# Microcontroller.net
KiCad netlist of a schematic drawn in Altium Designer
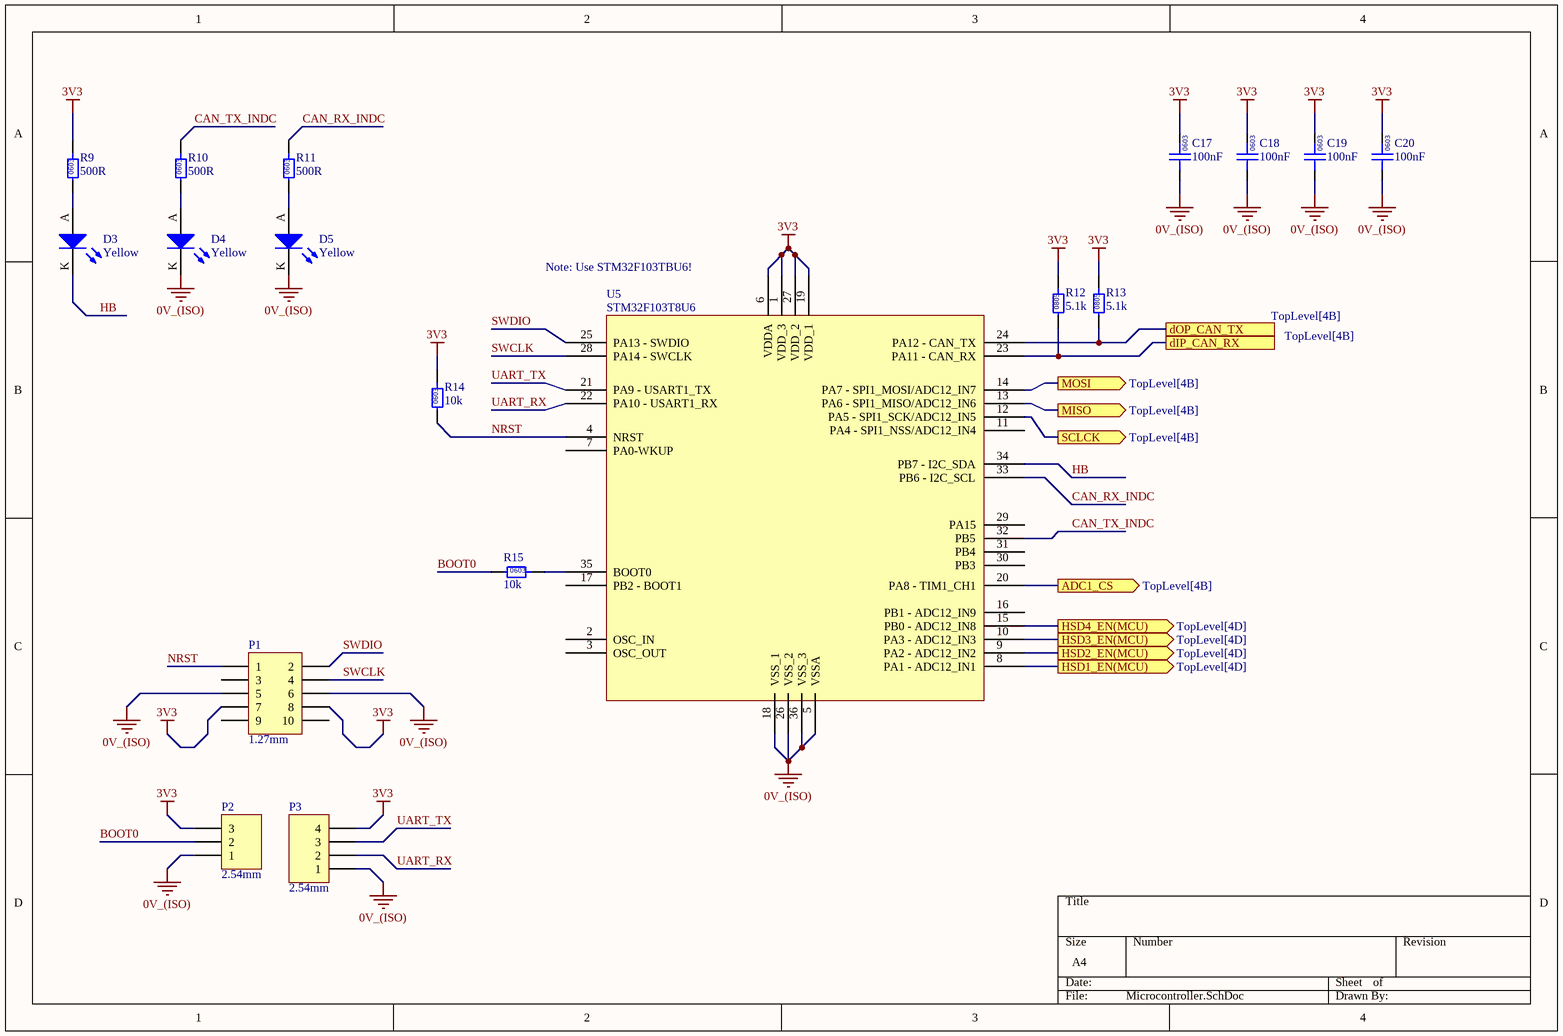
[diagram p0: Microcontroller.SchDoc]

(export (version "E")
  (design (tool "Eeschema 10.0.6"))
  (components
    (comp (ref "C17")
      (value "100nF")
      (footprint "0603")
      (fields
        (field (name "PART NUMBER") "GCM188L81H104KA57D")
        (field (name "MANUFACTURER") "muRata")
        (field (name "TOLERANCE") "±10%")
      )
      (libsource (lib "ts_standard_library") (part "Capacitor 0603"))
    )
    (comp (ref "C18")
      (value "100nF")
      (footprint "0603")
      (fields
        (field (name "PART NUMBER") "GCM188L81H104KA57D")
        (field (name "MANUFACTURER") "muRata")
        (field (name "TOLERANCE") "±10%")
      )
      (libsource (lib "ts_standard_library") (part "Capacitor 0603"))
    )
    (comp (ref "C19")
      (value "100nF")
      (footprint "0603")
      (fields
        (field (name "PART NUMBER") "GCM188L81H104KA57D")
        (field (name "MANUFACTURER") "muRata")
        (field (name "TOLERANCE") "±10%")
      )
      (libsource (lib "ts_standard_library") (part "Capacitor 0603"))
    )
    (comp (ref "C20")
      (value "100nF")
      (footprint "0603")
      (fields
        (field (name "PART NUMBER") "GCM188L81H104KA57D")
        (field (name "MANUFACTURER") "muRata")
        (field (name "TOLERANCE") "±10%")
      )
      (libsource (lib "ts_standard_library") (part "Capacitor 0603"))
    )
    (comp (ref "D3")
      (value "Yellow")
      (footprint "0805 LED")
      (description "Yellow LED Indication - Discrete 1.75V 0805 (2012 Metric)")
      (fields (field (name "PART NUMBER") "SML-211YTT86") (field (name "MANUFACTURER") "ROHM Semiconductor"))
      (libsource (lib "ts_standard_library") (part "LED"))
    )
    (comp (ref "D4")
      (value "Yellow")
      (footprint "0805 LED")
      (description "Yellow LED Indication - Discrete 1.75V 0805 (2012 Metric)")
      (fields (field (name "PART NUMBER") "SML-211YTT86") (field (name "MANUFACTURER") "ROHM Semiconductor"))
      (libsource (lib "ts_standard_library") (part "LED"))
    )
    (comp (ref "D5")
      (value "Yellow")
      (footprint "0805 LED")
      (description "Yellow LED Indication - Discrete 1.75V 0805 (2012 Metric)")
      (fields (field (name "PART NUMBER") "SML-211YTT86") (field (name "MANUFACTURER") "ROHM Semiconductor"))
      (libsource (lib "ts_standard_library") (part "LED"))
    )
    (comp (ref "P1")
      (value "1.27mm")
      (footprint "3221-10-0300-00")
      (fields
        (field (name "PART NUMBER") "SMD 1.27mm Header 2x5 (3221-10-0300-00)")
        (field (name "CONTACT") "NA")
      )
      (libsource (lib "ts_standard_connectors") (part "Header 2x5"))
    )
    (comp (ref "P2")
      (value "2.54mm")
      (footprint "TH 2.54mm Header 1x3")
      (fields (field (name "PART NUMBER") "TH 2.54mm Header 1x3") (field (name "CONTACT") "NA"))
      (libsource (lib "ts_standard_connectors") (part "Header 1x3"))
    )
    (comp (ref "P3")
      (value "2.54mm")
      (footprint "TH 2.54mm Header 1x4")
      (fields (field (name "PART NUMBER") "TH 2.54mm Header 1x4") (field (name "CONTACT") "NA"))
      (libsource (lib "ts_standard_connectors") (part "Header 1x4"))
    )
    (comp (ref "R9")
      (value "500R")
      (footprint "0603")
      (fields
        (field (name "PART NUMBER") "RT0603BRD07500RL")
        (field (name "MANUFACTURER") "YAGEO")
        (field (name "TOLERANCE") "0.01")
      )
      (libsource (lib "ts_standard_library") (part "Resistor 0603"))
    )
    (comp (ref "R10")
      (value "500R")
      (footprint "0603")
      (fields
        (field (name "PART NUMBER") "RT0603BRD07500RL")
        (field (name "MANUFACTURER") "YAGEO")
        (field (name "TOLERANCE") "0.01")
      )
      (libsource (lib "ts_standard_library") (part "Resistor 0603"))
    )
    (comp (ref "R11")
      (value "500R")
      (footprint "0603")
      (fields
        (field (name "PART NUMBER") "RT0603BRD07500RL")
        (field (name "MANUFACTURER") "YAGEO")
        (field (name "TOLERANCE") "0.01")
      )
      (libsource (lib "ts_standard_library") (part "Resistor 0603"))
    )
    (comp (ref "R12")
      (value "5.1k")
      (footprint "0805")
      (fields
        (field (name "PART NUMBER") "RC0805FR075K1L")
        (field (name "MANUFACTURER") "YAGEO")
        (field (name "TOLERANCE") "0.01")
      )
      (libsource (lib "ts_standard_library") (part "Resistor 0805"))
    )
    (comp (ref "R13")
      (value "5.1k")
      (footprint "0805")
      (fields
        (field (name "PART NUMBER") "RC0805FR075K1L")
        (field (name "MANUFACTURER") "YAGEO")
        (field (name "TOLERANCE") "0.01")
      )
      (libsource (lib "ts_standard_library") (part "Resistor 0805"))
    )
    (comp (ref "R14")
      (value "10k")
      (footprint "0603")
      (fields
        (field (name "PART NUMBER") "RC0603FR-0710KL")
        (field (name "MANUFACTURER") "YAGEO")
        (field (name "TOLERANCE") "0.01")
      )
      (libsource (lib "ts_standard_library") (part "Resistor 0603"))
    )
    (comp (ref "R15")
      (value "10k")
      (footprint "0603")
      (fields
        (field (name "PART NUMBER") "RC0603FR-0710KL")
        (field (name "MANUFACTURER") "YAGEO")
        (field (name "TOLERANCE") "0.01")
      )
      (libsource (lib "ts_standard_library") (part "Resistor 0603"))
    )
    (comp (ref "U5")
      (value "STM32F103T8U6")
      (footprint "STM_QFN-36")
      (description "ARM® Cortex®-M3 STM32F1 Microcontroller IC 32-Bit 72MHz 64KB (64K x 8) FLASH QFN")
      (fields (field (name "MANUFACTURER") "ST Microelectronics"))
      (libsource (lib "ts_standard_library") (part "STM32F103T8U6"))
    )
  )
  (nets
    (net (code "1") (name "/ADC1_CS") (class "Default")
      (node (ref "U5") (pin "20") (pinfunction "PA8_-_TIM1_CH1_20") (pintype "passive"))
    )
    (net (code "2") (name "/BOOT0") (class "Default")
      (node (ref "P2") (pin "2") (pinfunction "2_2") (pintype "passive"))
      (node (ref "R15") (pin "1") (pinfunction "1_1") (pintype "passive"))
    )
    (net (code "3") (name "/CAN_RX_INDC") (class "Default")
      (node (ref "R11") (pin "2") (pinfunction "2_2") (pintype "passive"))
      (node (ref "U5") (pin "33") (pinfunction "PB6_-_I2C_SCL_33") (pintype "passive"))
    )
    (net (code "4") (name "/CAN_TX_INDC") (class "Default")
      (node (ref "R10") (pin "2") (pinfunction "2_2") (pintype "passive"))
      (node (ref "U5") (pin "32") (pinfunction "PB5_32") (pintype "passive"))
    )
    (net (code "5") (name "/HB") (class "Default")
      (node (ref "D3") (pin "K") (pinfunction "K_K") (pintype "passive"))
      (node (ref "U5") (pin "34") (pinfunction "PB7_-_I2C_SDA_34") (pintype "passive"))
    )
    (net (code "6") (name "/HSD1_EN(MCU)") (class "Default")
      (node (ref "U5") (pin "8") (pinfunction "PA1_-_ADC12_IN1_8") (pintype "passive"))
    )
    (net (code "7") (name "/HSD2_EN(MCU)") (class "Default")
      (node (ref "U5") (pin "9") (pinfunction "PA2_-_ADC12_IN2_9") (pintype "passive"))
    )
    (net (code "8") (name "/HSD3_EN(MCU)") (class "Default")
      (node (ref "U5") (pin "10") (pinfunction "PA3_-_ADC12_IN3_10") (pintype "passive"))
    )
    (net (code "9") (name "/HSD4_EN(MCU)") (class "Default")
      (node (ref "U5") (pin "15") (pinfunction "PB0_-_ADC12_IN8_15") (pintype "passive"))
    )
    (net (code "10") (name "/MISO") (class "Default")
      (node (ref "U5") (pin "13") (pinfunction "PA6_-_SPI1_MISO/ADC12_IN6_13") (pintype "passive"))
    )
    (net (code "11") (name "/MOSI") (class "Default")
      (node (ref "U5") (pin "14") (pinfunction "PA7_-_SPI1_MOSI/ADC12_IN7_14") (pintype "passive"))
    )
    (net (code "12") (name "/NRST") (class "Default")
      (node (ref "P1") (pin "1") (pinfunction "1_1") (pintype "passive"))
      (node (ref "R14") (pin "1") (pinfunction "1_1") (pintype "passive"))
      (node (ref "U5") (pin "4") (pinfunction "NRST_4") (pintype "passive"))
    )
    (net (code "13") (name "/SCLCK") (class "Default")
      (node (ref "U5") (pin "12") (pinfunction "PA5_-_SPI1_SCK/ADC12_IN5_12") (pintype "passive"))
    )
    (net (code "14") (name "/SWCLK") (class "Default")
      (node (ref "P1") (pin "4") (pinfunction "4_4") (pintype "passive"))
      (node (ref "U5") (pin "28") (pinfunction "PA14_-_SWCLK_28") (pintype "passive"))
    )
    (net (code "15") (name "/SWDIO") (class "Default")
      (node (ref "P1") (pin "2") (pinfunction "2_2") (pintype "passive"))
      (node (ref "U5") (pin "25") (pinfunction "PA13_-_SWDIO_25") (pintype "passive"))
    )
    (net (code "16") (name "/UART_RX") (class "Default")
      (node (ref "P3") (pin "2") (pinfunction "2_2") (pintype "passive"))
      (node (ref "U5") (pin "22") (pinfunction "PA10_-_USART1_RX_22") (pintype "passive"))
    )
    (net (code "17") (name "/UART_TX") (class "Default")
      (node (ref "P3") (pin "3") (pinfunction "3_3") (pintype "passive"))
      (node (ref "U5") (pin "21") (pinfunction "PA9_-_USART1_TX_21") (pintype "passive"))
    )
    (net (code "18") (name "/dIP_CAN_RX") (class "Default")
      (node (ref "R12") (pin "1") (pinfunction "1_1") (pintype "passive"))
      (node (ref "U5") (pin "23") (pinfunction "PA11_-_CAN_RX_23") (pintype "passive"))
    )
    (net (code "19") (name "/dOP_CAN_TX") (class "Default")
      (node (ref "R13") (pin "1") (pinfunction "1_1") (pintype "passive"))
      (node (ref "U5") (pin "24") (pinfunction "PA12_-_CAN_TX_24") (pintype "passive"))
    )
    (net (code "20") (name "0V_(ISO)") (class "Default")
      (node (ref "C17") (pin "1") (pinfunction "1_1") (pintype "passive"))
      (node (ref "C18") (pin "1") (pinfunction "1_1") (pintype "passive"))
      (node (ref "C19") (pin "1") (pinfunction "1_1") (pintype "passive"))
      (node (ref "C20") (pin "1") (pinfunction "1_1") (pintype "passive"))
      (node (ref "D4") (pin "K") (pinfunction "K_K") (pintype "passive"))
      (node (ref "D5") (pin "K") (pinfunction "K_K") (pintype "passive"))
      (node (ref "P1") (pin "5") (pinfunction "5_5") (pintype "passive"))
      (node (ref "P1") (pin "6") (pinfunction "6_6") (pintype "passive"))
      (node (ref "P2") (pin "1") (pinfunction "1_1") (pintype "passive"))
      (node (ref "P3") (pin "1") (pinfunction "1_1") (pintype "passive"))
      (node (ref "U5") (pin "18") (pinfunction "VSS_1_18") (pintype "passive"))
      (node (ref "U5") (pin "26") (pinfunction "VSS_2_26") (pintype "passive"))
      (node (ref "U5") (pin "36") (pinfunction "VSS_3_36") (pintype "passive"))
      (node (ref "U5") (pin "5") (pinfunction "VSSA_5") (pintype "passive"))
    )
    (net (code "21") (name "3V3") (class "Default")
      (node (ref "C17") (pin "2") (pinfunction "2_2") (pintype "passive"))
      (node (ref "C18") (pin "2") (pinfunction "2_2") (pintype "passive"))
      (node (ref "C19") (pin "2") (pinfunction "2_2") (pintype "passive"))
      (node (ref "C20") (pin "2") (pinfunction "2_2") (pintype "passive"))
      (node (ref "P1") (pin "7") (pinfunction "7_7") (pintype "passive"))
      (node (ref "P1") (pin "8") (pinfunction "8_8") (pintype "passive"))
      (node (ref "P2") (pin "3") (pinfunction "3_3") (pintype "passive"))
      (node (ref "P3") (pin "4") (pinfunction "4_4") (pintype "passive"))
      (node (ref "R12") (pin "2") (pinfunction "2_2") (pintype "passive"))
      (node (ref "R13") (pin "2") (pinfunction "2_2") (pintype "passive"))
      (node (ref "R14") (pin "2") (pinfunction "2_2") (pintype "passive"))
      (node (ref "R9") (pin "2") (pinfunction "2_2") (pintype "passive"))
      (node (ref "U5") (pin "1") (pinfunction "VDD_3_1") (pintype "passive"))
      (node (ref "U5") (pin "19") (pinfunction "VDD_1_19") (pintype "passive"))
      (node (ref "U5") (pin "27") (pinfunction "VDD_2_27") (pintype "passive"))
      (node (ref "U5") (pin "6") (pinfunction "VDDA_6") (pintype "passive"))
    )
    (net (code "22") (name "Net-(D3-PadA)") (class "Default")
      (node (ref "D3") (pin "A") (pinfunction "A_A") (pintype "passive"))
      (node (ref "R9") (pin "1") (pinfunction "1_1") (pintype "passive"))
    )
    (net (code "23") (name "Net-(D4-PadA)") (class "Default")
      (node (ref "D4") (pin "A") (pinfunction "A_A") (pintype "passive"))
      (node (ref "R10") (pin "1") (pinfunction "1_1") (pintype "passive"))
    )
    (net (code "24") (name "Net-(D5-PadA)") (class "Default")
      (node (ref "D5") (pin "A") (pinfunction "A_A") (pintype "passive"))
      (node (ref "R11") (pin "1") (pinfunction "1_1") (pintype "passive"))
    )
    (net (code "25") (name "Net-(U5-BOOT0)") (class "Default")
      (node (ref "R15") (pin "2") (pinfunction "2_2") (pintype "passive"))
      (node (ref "U5") (pin "35") (pinfunction "BOOT0_35") (pintype "passive"))
    )
    (net (code "26") (name "unconnected-(P1-Pad3)") (class "Default")
      (node (ref "P1") (pin "3") (pinfunction "3_3") (pintype "passive"))
    )
    (net (code "27") (name "unconnected-(P1-Pad9)") (class "Default")
      (node (ref "P1") (pin "9") (pinfunction "9_9") (pintype "passive"))
    )
    (net (code "28") (name "unconnected-(P1-Pad10)") (class "Default")
      (node (ref "P1") (pin "10") (pinfunction "10_10") (pintype "passive"))
    )
    (net (code "29") (name "unconnected-(U5-OSC_IN-Pad2)") (class "Default")
      (node (ref "U5") (pin "2") (pinfunction "OSC_IN_2") (pintype "passive"))
    )
    (net (code "30") (name "unconnected-(U5-OSC_OUT-Pad3)") (class "Default")
      (node (ref "U5") (pin "3") (pinfunction "OSC_OUT_3") (pintype "passive"))
    )
    (net (code "31") (name "unconnected-(U5-PA0-WKUP-Pad7)") (class "Default")
      (node (ref "U5") (pin "7") (pinfunction "PA0-WKUP_7") (pintype "passive"))
    )
    (net (code "32") (name "unconnected-(U5-PA4_-_SPI1_NSS{slash}ADC12_IN4-Pad11)") (class "Default")
      (node (ref "U5") (pin "11") (pinfunction "PA4_-_SPI1_NSS/ADC12_IN4_11") (pintype "passive"))
    )
    (net (code "33") (name "unconnected-(U5-PA15-Pad29)") (class "Default")
      (node (ref "U5") (pin "29") (pinfunction "PA15_29") (pintype "passive"))
    )
    (net (code "34") (name "unconnected-(U5-PB1_-_ADC12_IN9-Pad16)") (class "Default")
      (node (ref "U5") (pin "16") (pinfunction "PB1_-_ADC12_IN9_16") (pintype "passive"))
    )
    (net (code "35") (name "unconnected-(U5-PB2_-_BOOT1-Pad17)") (class "Default")
      (node (ref "U5") (pin "17") (pinfunction "PB2_-_BOOT1_17") (pintype "passive"))
    )
    (net (code "36") (name "unconnected-(U5-PB3-Pad30)") (class "Default")
      (node (ref "U5") (pin "30") (pinfunction "PB3_30") (pintype "passive"))
    )
    (net (code "37") (name "unconnected-(U5-PB4-Pad31)") (class "Default")
      (node (ref "U5") (pin "31") (pinfunction "PB4_31") (pintype "passive"))
    )
  )
)
